# 263-15_2.net
KiCad netlist of a schematic drawn in Altium Designer
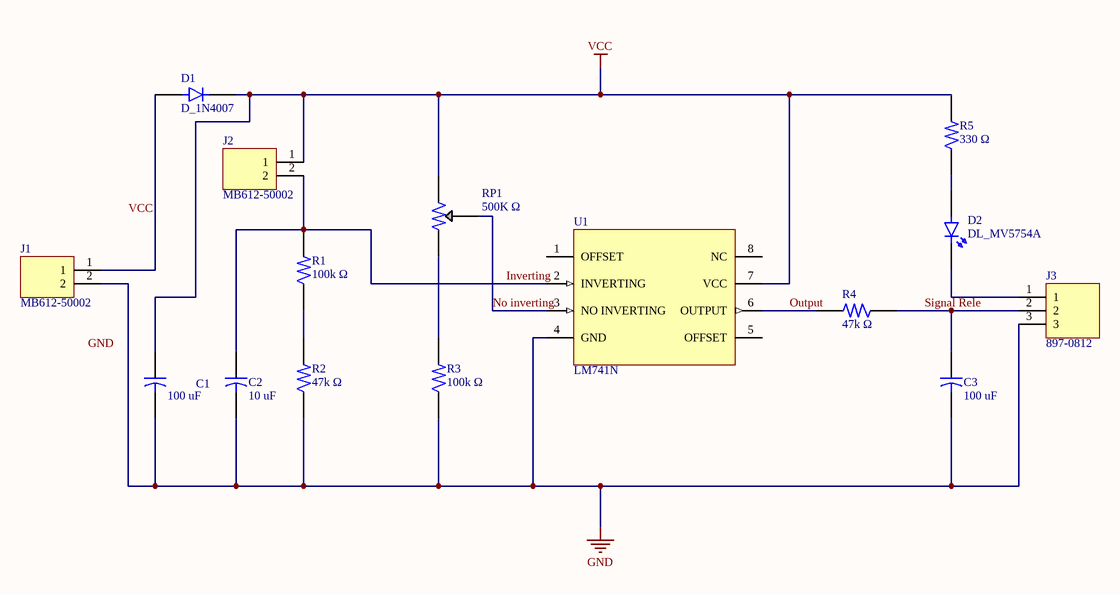
[diagram p0: 263-15.2.SchDoc]

(export (version "E")
  (design (tool "Eeschema 10.0.6"))
  (components
    (comp (ref "C1")
      (value "100 uF")
      (footprint "CAP_2mm")
      (description "Capacitor")
      (fields (field (name "Comment") "CAP_100uF_16V") (field (name "PUBLISHER") "Altium Limited"))
      (libsource (lib "Capacitors") (part "CAP_100uF_16V"))
    )
    (comp (ref "C2")
      (value "10 uF")
      (footprint "CAP_1.5mm")
      (description "Capacitor")
      (fields (field (name "Comment") "CAP_10uF_16V") (field (name "PUBLISHER") "Altium Limited"))
      (libsource (lib "Capacitors") (part "CAP_10uF_16V"))
    )
    (comp (ref "C3")
      (value "100 uF")
      (footprint "CAP_2mm")
      (description "Capacitor")
      (fields (field (name "Comment") "CAP_100uF_16V") (field (name "PUBLISHER") "Altium Limited"))
      (libsource (lib "Capacitors") (part "CAP_100uF_16V"))
    )
    (comp (ref "D1")
      (value "D_1N4007")
      (footprint "DO-41")
      (description "Diode Standard 1000 V 1A Through Hole DO-41")
      (libsource (lib "Diodes") (part "D_1N4007"))
    )
    (comp (ref "D2")
      (value "DL_MV5754A")
      (footprint "LED-2.54mm")
      (description "Diode Led Red")
      (fields (field (name "MPN") "MV5754A"))
      (libsource (lib "Diodes") (part "DL_MV5754A"))
    )
    (comp (ref "J1")
      (value "CON_F_2_MB612-50002")
      (footprint "Conectors THC:CON_2_5mm")
      (fields (field (name "MPN") "MB612-50002"))
      (libsource (lib "Conectors_THC") (part "CON_F_2_MB612-50002"))
    )
    (comp (ref "J2")
      (value "CON_F_2_MB612-50002")
      (footprint "Conectors THC:CON_2_5mm")
      (fields (field (name "MPN") "MB612-50002"))
      (libsource (lib "Conectors_THC") (part "CON_F_2_MB612-50002"))
    )
    (comp (ref "J3")
      (value "CON_F_3_897-0812")
      (footprint "CON_3_5mm")
      (fields (field (name "MPN") "897-0812"))
      (libsource (lib "Conectors_THC") (part "CON_F_3_897-0812"))
    )
    (comp (ref "R1")
      (value "100k Ω")
      (footprint "RESISTOR-8mm")
      (fields (field (name "Comment") "R_100K_THC_0.25W"))
      (libsource (lib "Resistors") (part "R_100K_THC_0.25W"))
    )
    (comp (ref "R2")
      (value "47k Ω")
      (footprint "RESISTOR-8mm")
      (fields (field (name "Comment") "R_47K_THC_0.25W"))
      (libsource (lib "Resistors") (part "R_47K_THC_0.25W"))
    )
    (comp (ref "R3")
      (value "100k Ω")
      (footprint "RESISTOR-8mm")
      (fields (field (name "Comment") "R_100K_THC_0.25W"))
      (libsource (lib "Resistors") (part "R_100K_THC_0.25W"))
    )
    (comp (ref "R4")
      (value "47k Ω")
      (footprint "RESISTOR-8mm")
      (fields (field (name "Comment") "R_47K_THC_0.25W"))
      (libsource (lib "Resistors") (part "R_47K_THC_0.25W"))
    )
    (comp (ref "R5")
      (value "330 Ω")
      (footprint "RESISTOR-8mm")
      (fields (field (name "Comment") "R_330_THC_0.25W"))
      (libsource (lib "Resistors") (part "R_330_THC_0.25W"))
    )
    (comp (ref "RP1")
      (value "500K Ω")
      (footprint "RP_RKT6V")
      (fields (field (name "MPN") "RKT6V-H") (field (name "Comment") "RP_RKT6V-H"))
      (libsource (lib "Potentiometers") (part "RP_RKT6V-H"))
    )
    (comp (ref "U1")
      (value "IC_LM741")
      (footprint "PDIP-8_THC")
      (fields (field (name "MPN") "LM741N"))
      (libsource (lib "Integrated Circuit") (part "IC_LM741"))
    )
  )
  (nets
    (net (code "1") (name "/Inverting") (class "Default")
      (node (ref "C2") (pin "1") (pinfunction "1_1") (pintype "passive"))
      (node (ref "J2") (pin "2") (pinfunction "2_2") (pintype "passive"))
      (node (ref "R1") (pin "2") (pintype "passive"))
      (node (ref "U1") (pin "2") (pinfunction "INVERTING_2") (pintype "input"))
    )
    (net (code "2") (name "/No inverting") (class "Default")
      (node (ref "RP1") (pin "2") (pinfunction "2_2") (pintype "passive"))
      (node (ref "U1") (pin "3") (pinfunction "NO_INVERTING_3") (pintype "input"))
    )
    (net (code "3") (name "/Output") (class "Default")
      (node (ref "R4") (pin "2") (pintype "passive"))
      (node (ref "U1") (pin "6") (pinfunction "OUTPUT_6") (pintype "output"))
    )
    (net (code "4") (name "/Signal Rele") (class "Default")
      (node (ref "C3") (pin "1") (pinfunction "1_1") (pintype "passive"))
      (node (ref "J3") (pin "2") (pinfunction "2_2") (pintype "passive"))
      (node (ref "R4") (pin "1") (pinfunction "1_1") (pintype "passive"))
    )
    (net (code "5") (name "GND") (class "Default")
      (node (ref "C1") (pin "2") (pinfunction "2_2") (pintype "passive"))
      (node (ref "C2") (pin "2") (pinfunction "2_2") (pintype "passive"))
      (node (ref "C3") (pin "2") (pinfunction "2_2") (pintype "passive"))
      (node (ref "J1") (pin "2") (pinfunction "2_2") (pintype "passive"))
      (node (ref "J3") (pin "3") (pinfunction "3_3") (pintype "passive"))
      (node (ref "R2") (pin "1") (pinfunction "1_1") (pintype "passive"))
      (node (ref "R3") (pin "1") (pinfunction "1_1") (pintype "passive"))
      (node (ref "U1") (pin "4") (pinfunction "GND_4") (pintype "passive"))
    )
    (net (code "6") (name "Net-(D1-PadA)") (class "Default")
      (node (ref "D1") (pin "A") (pinfunction "A_A") (pintype "passive"))
      (node (ref "J1") (pin "1") (pinfunction "1_1") (pintype "passive"))
    )
    (net (code "7") (name "Net-(D2-PadA)") (class "Default")
      (node (ref "D2") (pin "A") (pinfunction "A_A") (pintype "passive"))
      (node (ref "R5") (pin "1") (pinfunction "1_1") (pintype "passive"))
    )
    (net (code "8") (name "Net-(D2-PadK)") (class "Default")
      (node (ref "D2") (pin "K") (pinfunction "K_K") (pintype "passive"))
      (node (ref "J3") (pin "1") (pinfunction "1_1") (pintype "passive"))
    )
    (net (code "9") (name "Net-(R1-Pad1)") (class "Default")
      (node (ref "R1") (pin "1") (pinfunction "1_1") (pintype "passive"))
      (node (ref "R2") (pin "2") (pintype "passive"))
    )
    (net (code "10") (name "Net-(R3-Pad2)") (class "Default")
      (node (ref "R3") (pin "2") (pintype "passive"))
      (node (ref "RP1") (pin "3") (pinfunction "3_3") (pintype "passive"))
    )
    (net (code "11") (name "VCC") (class "Default")
      (node (ref "C1") (pin "1") (pinfunction "1_1") (pintype "passive"))
      (node (ref "D1") (pin "K") (pinfunction "K_K") (pintype "passive"))
      (node (ref "J2") (pin "1") (pinfunction "1_1") (pintype "passive"))
      (node (ref "R5") (pin "2") (pintype "passive"))
      (node (ref "RP1") (pin "1") (pinfunction "1_1") (pintype "passive"))
      (node (ref "U1") (pin "7") (pinfunction "VCC_7") (pintype "power_in"))
    )
    (net (code "12") (name "unconnected-(U1-NC-Pad8)") (class "Default")
      (node (ref "U1") (pin "8") (pinfunction "NC_8") (pintype "passive"))
    )
    (net (code "13") (name "unconnected-(U1-OFFSET-Pad1)") (class "Default")
      (node (ref "U1") (pin "1") (pinfunction "OFFSET_1") (pintype "passive"))
    )
    (net (code "14") (name "unconnected-(U1-OFFSET-Pad5)") (class "Default")
      (node (ref "U1") (pin "5") (pinfunction "OFFSET_5") (pintype "passive"))
    )
  )
)
